# AquModule.net
KiCad netlist of a schematic drawn in EAGLE
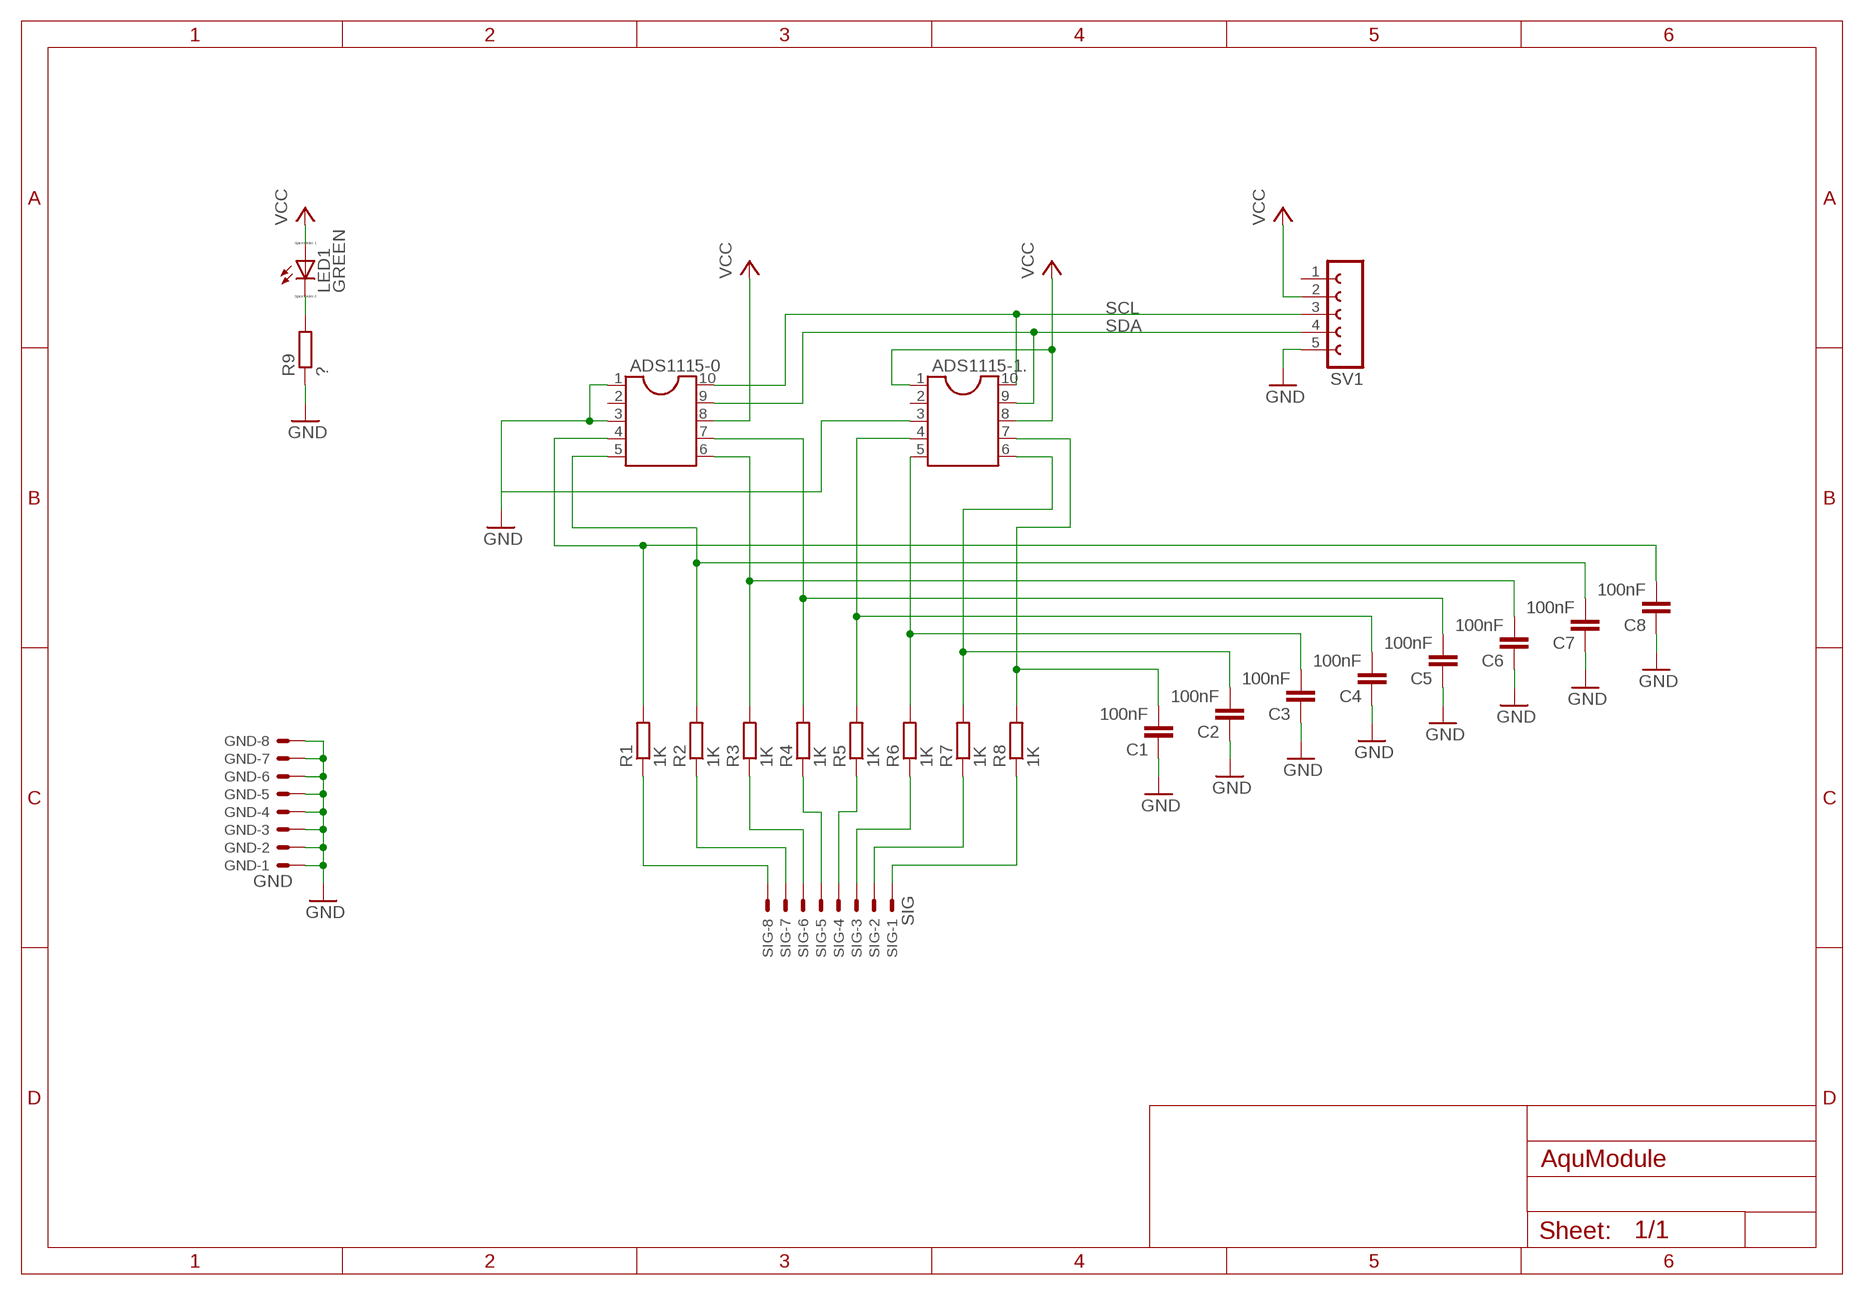
[diagram p0: schematic, sheet 1]

(export (version "E")
  (design (tool "Eeschema 10.0.6"))
  (components
    (comp (ref "ADS1115-0")
      (value "DIL10")
      (footprint "eagle-import:DIL10")
      (libsource (lib "eagle-import") (part "DIL10"))
    )
    (comp (ref "ADS1115-1.")
      (value "DIL10")
      (footprint "eagle-import:DIL10")
      (libsource (lib "eagle-import") (part "DIL10"))
    )
    (comp (ref "C1")
      (value "100nF")
      (footprint "eagle-import:C1005")
      (libsource (lib "eagle-import") (part "C-EUC1005"))
    )
    (comp (ref "C2")
      (value "100nF")
      (footprint "eagle-import:C1005")
      (libsource (lib "eagle-import") (part "C-EUC1005"))
    )
    (comp (ref "C3")
      (value "100nF")
      (footprint "eagle-import:C1005")
      (libsource (lib "eagle-import") (part "C-EUC1005"))
    )
    (comp (ref "C4")
      (value "100nF")
      (footprint "eagle-import:C1005")
      (libsource (lib "eagle-import") (part "C-EUC1005"))
    )
    (comp (ref "C5")
      (value "100nF")
      (footprint "eagle-import:C1005")
      (libsource (lib "eagle-import") (part "C-EUC1005"))
    )
    (comp (ref "C6")
      (value "100nF")
      (footprint "eagle-import:C1005")
      (libsource (lib "eagle-import") (part "C-EUC1005"))
    )
    (comp (ref "C7")
      (value "100nF")
      (footprint "eagle-import:C1005")
      (libsource (lib "eagle-import") (part "C-EUC1005"))
    )
    (comp (ref "C8")
      (value "100nF")
      (footprint "eagle-import:C1005")
      (libsource (lib "eagle-import") (part "C-EUC1005"))
    )
    (comp (ref "GND")
      (value "GND")
      (footprint "eagle-import:15-91-08")
      (libsource (lib "eagle-import") (part "C-GRID-08-15-91"))
    )
    (comp (ref "LED1")
      (value "GREEN")
      (footprint "eagle-import:LED_LD260")
      (libsource (lib "eagle-import") (part "LED_ELD260"))
    )
    (comp (ref "R1")
      (value "1K")
      (footprint "eagle-import:R0603")
      (libsource (lib "eagle-import") (part "R-EU_R0603"))
    )
    (comp (ref "R2")
      (value "1K")
      (footprint "eagle-import:R0603")
      (libsource (lib "eagle-import") (part "R-EU_R0603"))
    )
    (comp (ref "R3")
      (value "1K")
      (footprint "eagle-import:R0603")
      (libsource (lib "eagle-import") (part "R-EU_R0603"))
    )
    (comp (ref "R4")
      (value "1K")
      (footprint "eagle-import:R0603")
      (libsource (lib "eagle-import") (part "R-EU_R0603"))
    )
    (comp (ref "R5")
      (value "1K")
      (footprint "eagle-import:R0603")
      (libsource (lib "eagle-import") (part "R-EU_R0603"))
    )
    (comp (ref "R6")
      (value "1K")
      (footprint "eagle-import:R0603")
      (libsource (lib "eagle-import") (part "R-EU_R0603"))
    )
    (comp (ref "R7")
      (value "1K")
      (footprint "eagle-import:R0603")
      (libsource (lib "eagle-import") (part "R-EU_R0603"))
    )
    (comp (ref "R8")
      (value "1K")
      (footprint "eagle-import:R0603")
      (libsource (lib "eagle-import") (part "R-EU_R0603"))
    )
    (comp (ref "R9")
      (value "?")
      (footprint "eagle-import:0207_2V")
      (libsource (lib "eagle-import") (part "R-EU_0207/2V"))
    )
    (comp (ref "SIG")
      (value "SIG")
      (footprint "eagle-import:15-91-08")
      (libsource (lib "eagle-import") (part "C-GRID-08-15-91"))
    )
    (comp (ref "SV1")
      (value "FE05-1")
      (footprint "eagle-import:FE05-1")
      (libsource (lib "eagle-import") (part "FE05-1"))
    )
  )
  (nets
    (net (code "1") (name "/SCL") (class "Default")
      (node (ref "ADS1115-0") (pin "10") (pinfunction "10_10") (pintype "passive"))
      (node (ref "ADS1115-1.") (pin "10") (pinfunction "10_10") (pintype "passive"))
      (node (ref "SV1") (pin "3") (pinfunction "3_3") (pintype "passive"))
    )
    (net (code "2") (name "/SDA") (class "Default")
      (node (ref "ADS1115-0") (pin "9") (pinfunction "9_9") (pintype "passive"))
      (node (ref "ADS1115-1.") (pin "9") (pinfunction "9_9") (pintype "passive"))
      (node (ref "SV1") (pin "4") (pinfunction "4_4") (pintype "passive"))
    )
    (net (code "3") (name "GND") (class "Default")
      (node (ref "ADS1115-0") (pin "1") (pinfunction "1_1") (pintype "passive"))
      (node (ref "ADS1115-0") (pin "3") (pinfunction "3_3") (pintype "passive"))
      (node (ref "ADS1115-1.") (pin "3") (pinfunction "3_3") (pintype "passive"))
      (node (ref "C1") (pin "1") (pinfunction "1_1") (pintype "passive"))
      (node (ref "C2") (pin "1") (pinfunction "1_1") (pintype "passive"))
      (node (ref "C3") (pin "1") (pinfunction "1_1") (pintype "passive"))
      (node (ref "C4") (pin "1") (pinfunction "1_1") (pintype "passive"))
      (node (ref "C5") (pin "1") (pinfunction "1_1") (pintype "passive"))
      (node (ref "C6") (pin "1") (pinfunction "1_1") (pintype "passive"))
      (node (ref "C7") (pin "1") (pinfunction "1_1") (pintype "passive"))
      (node (ref "C8") (pin "1") (pinfunction "1_1") (pintype "passive"))
      (node (ref "GND") (pin "1") (pinfunction "S_1") (pintype "passive"))
      (node (ref "GND") (pin "2") (pinfunction "S_2") (pintype "passive"))
      (node (ref "GND") (pin "3") (pinfunction "S_3") (pintype "passive"))
      (node (ref "GND") (pin "4") (pinfunction "S_4") (pintype "passive"))
      (node (ref "GND") (pin "5") (pinfunction "S_5") (pintype "passive"))
      (node (ref "GND") (pin "6") (pinfunction "S_6") (pintype "passive"))
      (node (ref "GND") (pin "7") (pinfunction "S_7") (pintype "passive"))
      (node (ref "GND") (pin "8") (pinfunction "S_8") (pintype "passive"))
      (node (ref "R9") (pin "1") (pinfunction "1_1") (pintype "passive"))
      (node (ref "SV1") (pin "5") (pinfunction "5_5") (pintype "passive"))
    )
    (net (code "4") (name "Net-(ADS1115-0-Pad4)") (class "Default")
      (node (ref "ADS1115-0") (pin "4") (pinfunction "4_4") (pintype "passive"))
      (node (ref "C8") (pin "2") (pinfunction "2_2") (pintype "passive"))
      (node (ref "R1") (pin "2") (pinfunction "2_2") (pintype "passive"))
    )
    (net (code "5") (name "Net-(ADS1115-0-Pad5)") (class "Default")
      (node (ref "ADS1115-0") (pin "5") (pinfunction "5_5") (pintype "passive"))
      (node (ref "C7") (pin "2") (pinfunction "2_2") (pintype "passive"))
      (node (ref "R2") (pin "2") (pinfunction "2_2") (pintype "passive"))
    )
    (net (code "6") (name "Net-(ADS1115-0-Pad6)") (class "Default")
      (node (ref "ADS1115-0") (pin "6") (pinfunction "6_6") (pintype "passive"))
      (node (ref "C6") (pin "2") (pinfunction "2_2") (pintype "passive"))
      (node (ref "R3") (pin "2") (pinfunction "2_2") (pintype "passive"))
    )
    (net (code "7") (name "Net-(ADS1115-0-Pad7)") (class "Default")
      (node (ref "ADS1115-0") (pin "7") (pinfunction "7_7") (pintype "passive"))
      (node (ref "C5") (pin "2") (pinfunction "2_2") (pintype "passive"))
      (node (ref "R4") (pin "2") (pinfunction "2_2") (pintype "passive"))
    )
    (net (code "8") (name "Net-(ADS1115-1.-Pad4)") (class "Default")
      (node (ref "ADS1115-1.") (pin "4") (pinfunction "4_4") (pintype "passive"))
      (node (ref "C4") (pin "2") (pinfunction "2_2") (pintype "passive"))
      (node (ref "R5") (pin "2") (pinfunction "2_2") (pintype "passive"))
    )
    (net (code "9") (name "Net-(ADS1115-1.-Pad5)") (class "Default")
      (node (ref "ADS1115-1.") (pin "5") (pinfunction "5_5") (pintype "passive"))
      (node (ref "C3") (pin "2") (pinfunction "2_2") (pintype "passive"))
      (node (ref "R6") (pin "2") (pinfunction "2_2") (pintype "passive"))
    )
    (net (code "10") (name "Net-(ADS1115-1.-Pad6)") (class "Default")
      (node (ref "ADS1115-1.") (pin "6") (pinfunction "6_6") (pintype "passive"))
      (node (ref "C2") (pin "2") (pinfunction "2_2") (pintype "passive"))
      (node (ref "R7") (pin "2") (pinfunction "2_2") (pintype "passive"))
    )
    (net (code "11") (name "Net-(ADS1115-1.-Pad7)") (class "Default")
      (node (ref "ADS1115-1.") (pin "7") (pinfunction "7_7") (pintype "passive"))
      (node (ref "C1") (pin "2") (pinfunction "2_2") (pintype "passive"))
      (node (ref "R8") (pin "2") (pinfunction "2_2") (pintype "passive"))
    )
    (net (code "12") (name "Net-(LED1-C)") (class "Default")
      (node (ref "LED1") (pin "K") (pinfunction "C_K") (pintype "passive"))
      (node (ref "R9") (pin "2") (pinfunction "2_2") (pintype "passive"))
    )
    (net (code "13") (name "Net-(SIGA-S)") (class "Default")
      (node (ref "R8") (pin "1") (pinfunction "1_1") (pintype "passive"))
      (node (ref "SIG") (pin "1") (pinfunction "S_1") (pintype "passive"))
    )
    (net (code "14") (name "Net-(SIGB-S)") (class "Default")
      (node (ref "R7") (pin "1") (pinfunction "1_1") (pintype "passive"))
      (node (ref "SIG") (pin "2") (pinfunction "S_2") (pintype "passive"))
    )
    (net (code "15") (name "Net-(SIGC-S)") (class "Default")
      (node (ref "R6") (pin "1") (pinfunction "1_1") (pintype "passive"))
      (node (ref "SIG") (pin "3") (pinfunction "S_3") (pintype "passive"))
    )
    (net (code "16") (name "Net-(SIGD-S)") (class "Default")
      (node (ref "R5") (pin "1") (pinfunction "1_1") (pintype "passive"))
      (node (ref "SIG") (pin "4") (pinfunction "S_4") (pintype "passive"))
    )
    (net (code "17") (name "Net-(SIGE-S)") (class "Default")
      (node (ref "R4") (pin "1") (pinfunction "1_1") (pintype "passive"))
      (node (ref "SIG") (pin "5") (pinfunction "S_5") (pintype "passive"))
    )
    (net (code "18") (name "Net-(SIGF-S)") (class "Default")
      (node (ref "R3") (pin "1") (pinfunction "1_1") (pintype "passive"))
      (node (ref "SIG") (pin "6") (pinfunction "S_6") (pintype "passive"))
    )
    (net (code "19") (name "Net-(SIGG-S)") (class "Default")
      (node (ref "R2") (pin "1") (pinfunction "1_1") (pintype "passive"))
      (node (ref "SIG") (pin "7") (pinfunction "S_7") (pintype "passive"))
    )
    (net (code "20") (name "Net-(SIGH-S)") (class "Default")
      (node (ref "R1") (pin "1") (pinfunction "1_1") (pintype "passive"))
      (node (ref "SIG") (pin "8") (pinfunction "S_8") (pintype "passive"))
    )
    (net (code "21") (name "VCC") (class "Default")
      (node (ref "ADS1115-0") (pin "8") (pinfunction "8_8") (pintype "passive"))
      (node (ref "ADS1115-1.") (pin "1") (pinfunction "1_1") (pintype "passive"))
      (node (ref "ADS1115-1.") (pin "8") (pinfunction "8_8") (pintype "passive"))
      (node (ref "LED1") (pin "A") (pinfunction "A_A") (pintype "passive"))
      (node (ref "SV1") (pin "2") (pinfunction "2_2") (pintype "passive"))
    )
    (net (code "22") (name "unconnected-(ADS1115-0-Pad2)") (class "Default")
      (node (ref "ADS1115-0") (pin "2") (pinfunction "2_2") (pintype "passive"))
    )
    (net (code "23") (name "unconnected-(ADS1115-1.-Pad2)") (class "Default")
      (node (ref "ADS1115-1.") (pin "2") (pinfunction "2_2") (pintype "passive"))
    )
    (net (code "24") (name "unconnected-(SV1-Pad1)") (class "Default")
      (node (ref "SV1") (pin "1") (pinfunction "1_1") (pintype "passive"))
    )
  )
)
